# TopPanelV4.net
KiCad netlist of a schematic drawn in EAGLE
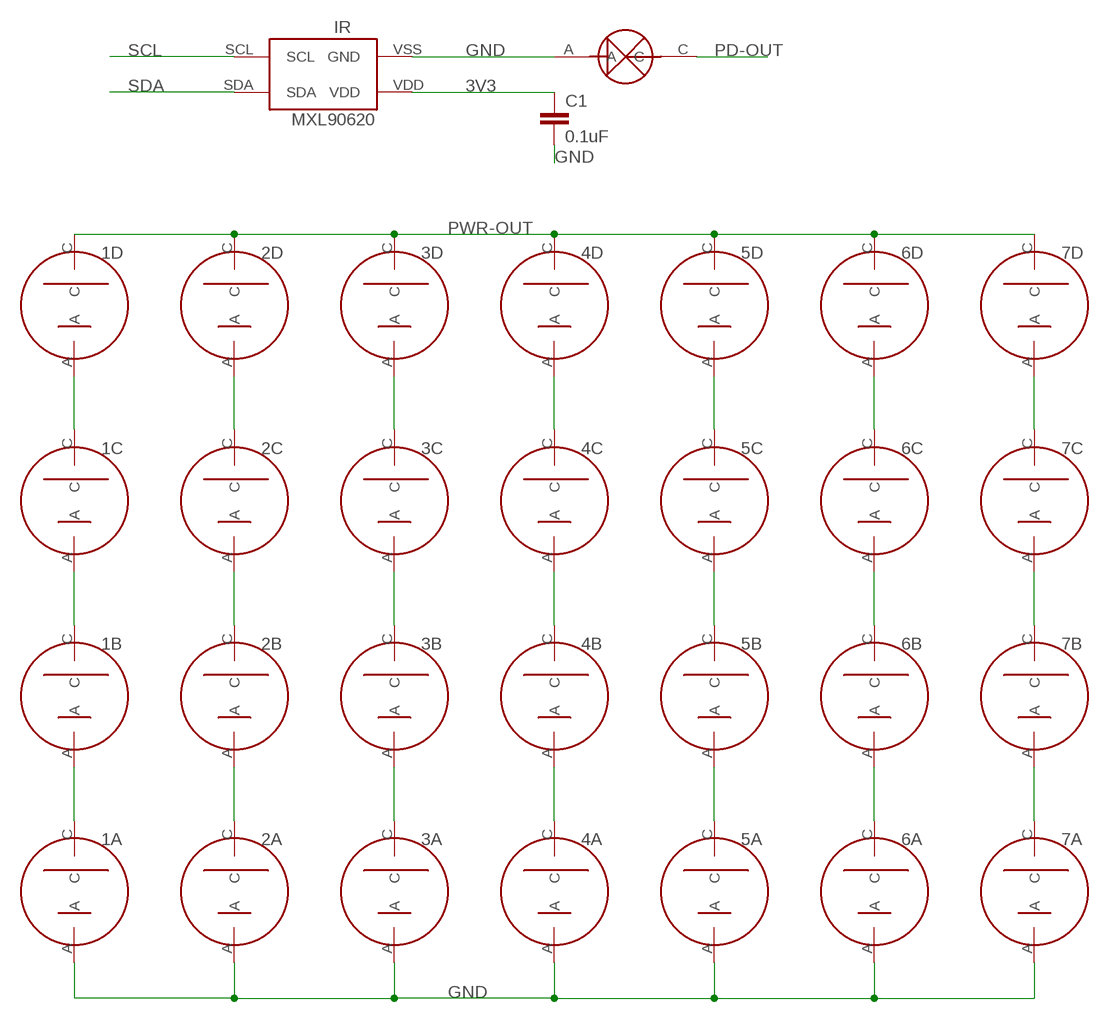
[diagram p0: schematic, sheet 1]

(export (version "E")
  (design (tool "Eeschema 10.0.6"))
  (components
    (comp (ref "1A")
      (value "NEWSOLARPANEL")
      (footprint "eagle-import:SOLARCELL2")
      (libsource (lib "eagle-import") (part "NEWSOLARPANEL"))
    )
    (comp (ref "1B")
      (value "NEWSOLARPANEL")
      (footprint "eagle-import:SOLARCELL2")
      (libsource (lib "eagle-import") (part "NEWSOLARPANEL"))
    )
    (comp (ref "1C")
      (value "NEWSOLARPANEL")
      (footprint "eagle-import:SOLARCELL2")
      (libsource (lib "eagle-import") (part "NEWSOLARPANEL"))
    )
    (comp (ref "1D")
      (value "NEWSOLARPANEL")
      (footprint "eagle-import:SOLARCELL2")
      (libsource (lib "eagle-import") (part "NEWSOLARPANEL"))
    )
    (comp (ref "2A")
      (value "NEWSOLARPANEL")
      (footprint "eagle-import:SOLARCELL2")
      (libsource (lib "eagle-import") (part "NEWSOLARPANEL"))
    )
    (comp (ref "2B")
      (value "NEWSOLARPANEL")
      (footprint "eagle-import:SOLARCELL2")
      (libsource (lib "eagle-import") (part "NEWSOLARPANEL"))
    )
    (comp (ref "2C")
      (value "NEWSOLARPANEL")
      (footprint "eagle-import:SOLARCELL2")
      (libsource (lib "eagle-import") (part "NEWSOLARPANEL"))
    )
    (comp (ref "2D")
      (value "NEWSOLARPANEL")
      (footprint "eagle-import:SOLARCELL2")
      (libsource (lib "eagle-import") (part "NEWSOLARPANEL"))
    )
    (comp (ref "3A")
      (value "NEWSOLARPANEL")
      (footprint "eagle-import:SOLARCELL2")
      (libsource (lib "eagle-import") (part "NEWSOLARPANEL"))
    )
    (comp (ref "3B")
      (value "NEWSOLARPANEL")
      (footprint "eagle-import:SOLARCELL2")
      (libsource (lib "eagle-import") (part "NEWSOLARPANEL"))
    )
    (comp (ref "3C")
      (value "NEWSOLARPANEL")
      (footprint "eagle-import:SOLARCELL2")
      (libsource (lib "eagle-import") (part "NEWSOLARPANEL"))
    )
    (comp (ref "3D")
      (value "NEWSOLARPANEL")
      (footprint "eagle-import:SOLARCELL2")
      (libsource (lib "eagle-import") (part "NEWSOLARPANEL"))
    )
    (comp (ref "4A")
      (value "NEWSOLARPANEL")
      (footprint "eagle-import:SOLARCELL2")
      (libsource (lib "eagle-import") (part "NEWSOLARPANEL"))
    )
    (comp (ref "4B")
      (value "NEWSOLARPANEL")
      (footprint "eagle-import:SOLARCELL2")
      (libsource (lib "eagle-import") (part "NEWSOLARPANEL"))
    )
    (comp (ref "4C")
      (value "NEWSOLARPANEL")
      (footprint "eagle-import:SOLARCELL2")
      (libsource (lib "eagle-import") (part "NEWSOLARPANEL"))
    )
    (comp (ref "4D")
      (value "NEWSOLARPANEL")
      (footprint "eagle-import:SOLARCELL2")
      (libsource (lib "eagle-import") (part "NEWSOLARPANEL"))
    )
    (comp (ref "5A")
      (value "NEWSOLARPANEL")
      (footprint "eagle-import:SOLARCELL2")
      (libsource (lib "eagle-import") (part "NEWSOLARPANEL"))
    )
    (comp (ref "5B")
      (value "NEWSOLARPANEL")
      (footprint "eagle-import:SOLARCELL2")
      (libsource (lib "eagle-import") (part "NEWSOLARPANEL"))
    )
    (comp (ref "5C")
      (value "NEWSOLARPANEL")
      (footprint "eagle-import:SOLARCELL2")
      (libsource (lib "eagle-import") (part "NEWSOLARPANEL"))
    )
    (comp (ref "5D")
      (value "NEWSOLARPANEL")
      (footprint "eagle-import:SOLARCELL2")
      (libsource (lib "eagle-import") (part "NEWSOLARPANEL"))
    )
    (comp (ref "6A")
      (value "NEWSOLARPANEL")
      (footprint "eagle-import:SOLARCELL2")
      (libsource (lib "eagle-import") (part "NEWSOLARPANEL"))
    )
    (comp (ref "6B")
      (value "NEWSOLARPANEL")
      (footprint "eagle-import:SOLARCELL2")
      (libsource (lib "eagle-import") (part "NEWSOLARPANEL"))
    )
    (comp (ref "6C")
      (value "NEWSOLARPANEL")
      (footprint "eagle-import:SOLARCELL2")
      (libsource (lib "eagle-import") (part "NEWSOLARPANEL"))
    )
    (comp (ref "6D")
      (value "NEWSOLARPANEL")
      (footprint "eagle-import:SOLARCELL2")
      (libsource (lib "eagle-import") (part "NEWSOLARPANEL"))
    )
    (comp (ref "7A")
      (value "NEWSOLARPANEL")
      (footprint "eagle-import:SOLARCELL2")
      (libsource (lib "eagle-import") (part "NEWSOLARPANEL"))
    )
    (comp (ref "7B")
      (value "NEWSOLARPANEL")
      (footprint "eagle-import:SOLARCELL2")
      (libsource (lib "eagle-import") (part "NEWSOLARPANEL"))
    )
    (comp (ref "7C")
      (value "NEWSOLARPANEL")
      (footprint "eagle-import:SOLARCELL2")
      (libsource (lib "eagle-import") (part "NEWSOLARPANEL"))
    )
    (comp (ref "7D")
      (value "NEWSOLARPANEL")
      (footprint "eagle-import:SOLARCELL2")
      (libsource (lib "eagle-import") (part "NEWSOLARPANEL"))
    )
    (comp (ref "C1")
      (value "0.1uF")
      (footprint "eagle-import:0805")
      (libsource (lib "eagle-import") (part "CAP0805"))
    )
    (comp (ref "IR")
      (value "MXL90620")
      (footprint "eagle-import:MXL90620")
      (libsource (lib "eagle-import") (part "MXL90620"))
    )
    (comp (ref "PD")
      (value "PHOTODETECTOR")
      (footprint "eagle-import:PHOTODECTORDEVICE2")
      (libsource (lib "eagle-import") (part "PHOTODETECTOR"))
    )
  )
  (nets
    (net (code "1") (name "/3V3") (class "Default")
      (node (ref "C1") (pin "1") (pinfunction "1_1") (pintype "passive"))
      (node (ref "IR") (pin "VDD") (pinfunction "VDD_VDD") (pintype "bidirectional"))
    )
    (net (code "2") (name "/GND") (class "Default")
      (node (ref "1A") (pin "A") (pinfunction "A_A") (pintype "bidirectional"))
      (node (ref "2A") (pin "A") (pinfunction "A_A") (pintype "bidirectional"))
      (node (ref "3A") (pin "A") (pinfunction "A_A") (pintype "bidirectional"))
      (node (ref "4A") (pin "A") (pinfunction "A_A") (pintype "bidirectional"))
      (node (ref "5A") (pin "A") (pinfunction "A_A") (pintype "bidirectional"))
      (node (ref "6A") (pin "A") (pinfunction "A_A") (pintype "bidirectional"))
      (node (ref "7A") (pin "A") (pinfunction "A_A") (pintype "bidirectional"))
      (node (ref "C1") (pin "2") (pinfunction "2_2") (pintype "passive"))
      (node (ref "IR") (pin "VSS") (pinfunction "GND_VSS") (pintype "bidirectional"))
      (node (ref "PD") (pin "A") (pinfunction "A_A") (pintype "bidirectional"))
    )
    (net (code "3") (name "/PD-OUT") (class "Default")
      (node (ref "PD") (pin "C") (pinfunction "C_C") (pintype "bidirectional"))
    )
    (net (code "4") (name "/PWR-OUT") (class "Default")
      (node (ref "1D") (pin "C") (pinfunction "C_C") (pintype "bidirectional"))
      (node (ref "2D") (pin "C") (pinfunction "C_C") (pintype "bidirectional"))
      (node (ref "3D") (pin "C") (pinfunction "C_C") (pintype "bidirectional"))
      (node (ref "4D") (pin "C") (pinfunction "C_C") (pintype "bidirectional"))
      (node (ref "5D") (pin "C") (pinfunction "C_C") (pintype "bidirectional"))
      (node (ref "6D") (pin "C") (pinfunction "C_C") (pintype "bidirectional"))
      (node (ref "7D") (pin "C") (pinfunction "C_C") (pintype "bidirectional"))
    )
    (net (code "5") (name "/SCL") (class "Default")
      (node (ref "IR") (pin "SCL") (pinfunction "SCL_SCL") (pintype "bidirectional"))
    )
    (net (code "6") (name "/SDA") (class "Default")
      (node (ref "IR") (pin "SDA") (pinfunction "SDA_SDA") (pintype "bidirectional"))
    )
    (net (code "7") (name "Net-(1A-PadC)") (class "Default")
      (node (ref "1A") (pin "C") (pinfunction "C_C") (pintype "bidirectional"))
      (node (ref "1B") (pin "A") (pinfunction "A_A") (pintype "bidirectional"))
    )
    (net (code "8") (name "Net-(1B-PadC)") (class "Default")
      (node (ref "1B") (pin "C") (pinfunction "C_C") (pintype "bidirectional"))
      (node (ref "1C") (pin "A") (pinfunction "A_A") (pintype "bidirectional"))
    )
    (net (code "9") (name "Net-(1C-PadC)") (class "Default")
      (node (ref "1C") (pin "C") (pinfunction "C_C") (pintype "bidirectional"))
      (node (ref "1D") (pin "A") (pinfunction "A_A") (pintype "bidirectional"))
    )
    (net (code "10") (name "Net-(2A-PadC)") (class "Default")
      (node (ref "2A") (pin "C") (pinfunction "C_C") (pintype "bidirectional"))
      (node (ref "2B") (pin "A") (pinfunction "A_A") (pintype "bidirectional"))
    )
    (net (code "11") (name "Net-(2B-PadC)") (class "Default")
      (node (ref "2B") (pin "C") (pinfunction "C_C") (pintype "bidirectional"))
      (node (ref "2C") (pin "A") (pinfunction "A_A") (pintype "bidirectional"))
    )
    (net (code "12") (name "Net-(2C-PadC)") (class "Default")
      (node (ref "2C") (pin "C") (pinfunction "C_C") (pintype "bidirectional"))
      (node (ref "2D") (pin "A") (pinfunction "A_A") (pintype "bidirectional"))
    )
    (net (code "13") (name "Net-(3A-PadC)") (class "Default")
      (node (ref "3A") (pin "C") (pinfunction "C_C") (pintype "bidirectional"))
      (node (ref "3B") (pin "A") (pinfunction "A_A") (pintype "bidirectional"))
    )
    (net (code "14") (name "Net-(3B-PadC)") (class "Default")
      (node (ref "3B") (pin "C") (pinfunction "C_C") (pintype "bidirectional"))
      (node (ref "3C") (pin "A") (pinfunction "A_A") (pintype "bidirectional"))
    )
    (net (code "15") (name "Net-(3C-PadC)") (class "Default")
      (node (ref "3C") (pin "C") (pinfunction "C_C") (pintype "bidirectional"))
      (node (ref "3D") (pin "A") (pinfunction "A_A") (pintype "bidirectional"))
    )
    (net (code "16") (name "Net-(4A-PadC)") (class "Default")
      (node (ref "4A") (pin "C") (pinfunction "C_C") (pintype "bidirectional"))
      (node (ref "4B") (pin "A") (pinfunction "A_A") (pintype "bidirectional"))
    )
    (net (code "17") (name "Net-(4B-PadC)") (class "Default")
      (node (ref "4B") (pin "C") (pinfunction "C_C") (pintype "bidirectional"))
      (node (ref "4C") (pin "A") (pinfunction "A_A") (pintype "bidirectional"))
    )
    (net (code "18") (name "Net-(4C-PadC)") (class "Default")
      (node (ref "4C") (pin "C") (pinfunction "C_C") (pintype "bidirectional"))
      (node (ref "4D") (pin "A") (pinfunction "A_A") (pintype "bidirectional"))
    )
    (net (code "19") (name "Net-(5A-PadC)") (class "Default")
      (node (ref "5A") (pin "C") (pinfunction "C_C") (pintype "bidirectional"))
      (node (ref "5B") (pin "A") (pinfunction "A_A") (pintype "bidirectional"))
    )
    (net (code "20") (name "Net-(5B-PadC)") (class "Default")
      (node (ref "5B") (pin "C") (pinfunction "C_C") (pintype "bidirectional"))
      (node (ref "5C") (pin "A") (pinfunction "A_A") (pintype "bidirectional"))
    )
    (net (code "21") (name "Net-(5C-PadC)") (class "Default")
      (node (ref "5C") (pin "C") (pinfunction "C_C") (pintype "bidirectional"))
      (node (ref "5D") (pin "A") (pinfunction "A_A") (pintype "bidirectional"))
    )
    (net (code "22") (name "Net-(6A-PadC)") (class "Default")
      (node (ref "6A") (pin "C") (pinfunction "C_C") (pintype "bidirectional"))
      (node (ref "6B") (pin "A") (pinfunction "A_A") (pintype "bidirectional"))
    )
    (net (code "23") (name "Net-(6B-PadC)") (class "Default")
      (node (ref "6B") (pin "C") (pinfunction "C_C") (pintype "bidirectional"))
      (node (ref "6C") (pin "A") (pinfunction "A_A") (pintype "bidirectional"))
    )
    (net (code "24") (name "Net-(6C-PadC)") (class "Default")
      (node (ref "6C") (pin "C") (pinfunction "C_C") (pintype "bidirectional"))
      (node (ref "6D") (pin "A") (pinfunction "A_A") (pintype "bidirectional"))
    )
    (net (code "25") (name "Net-(7A-PadC)") (class "Default")
      (node (ref "7A") (pin "C") (pinfunction "C_C") (pintype "bidirectional"))
      (node (ref "7B") (pin "A") (pinfunction "A_A") (pintype "bidirectional"))
    )
    (net (code "26") (name "Net-(7B-PadC)") (class "Default")
      (node (ref "7B") (pin "C") (pinfunction "C_C") (pintype "bidirectional"))
      (node (ref "7C") (pin "A") (pinfunction "A_A") (pintype "bidirectional"))
    )
    (net (code "27") (name "Net-(7C-PadC)") (class "Default")
      (node (ref "7C") (pin "C") (pinfunction "C_C") (pintype "bidirectional"))
      (node (ref "7D") (pin "A") (pinfunction "A_A") (pintype "bidirectional"))
    )
  )
)
